# Power_Supply.net
KiCad netlist of a schematic drawn in Altium Designer
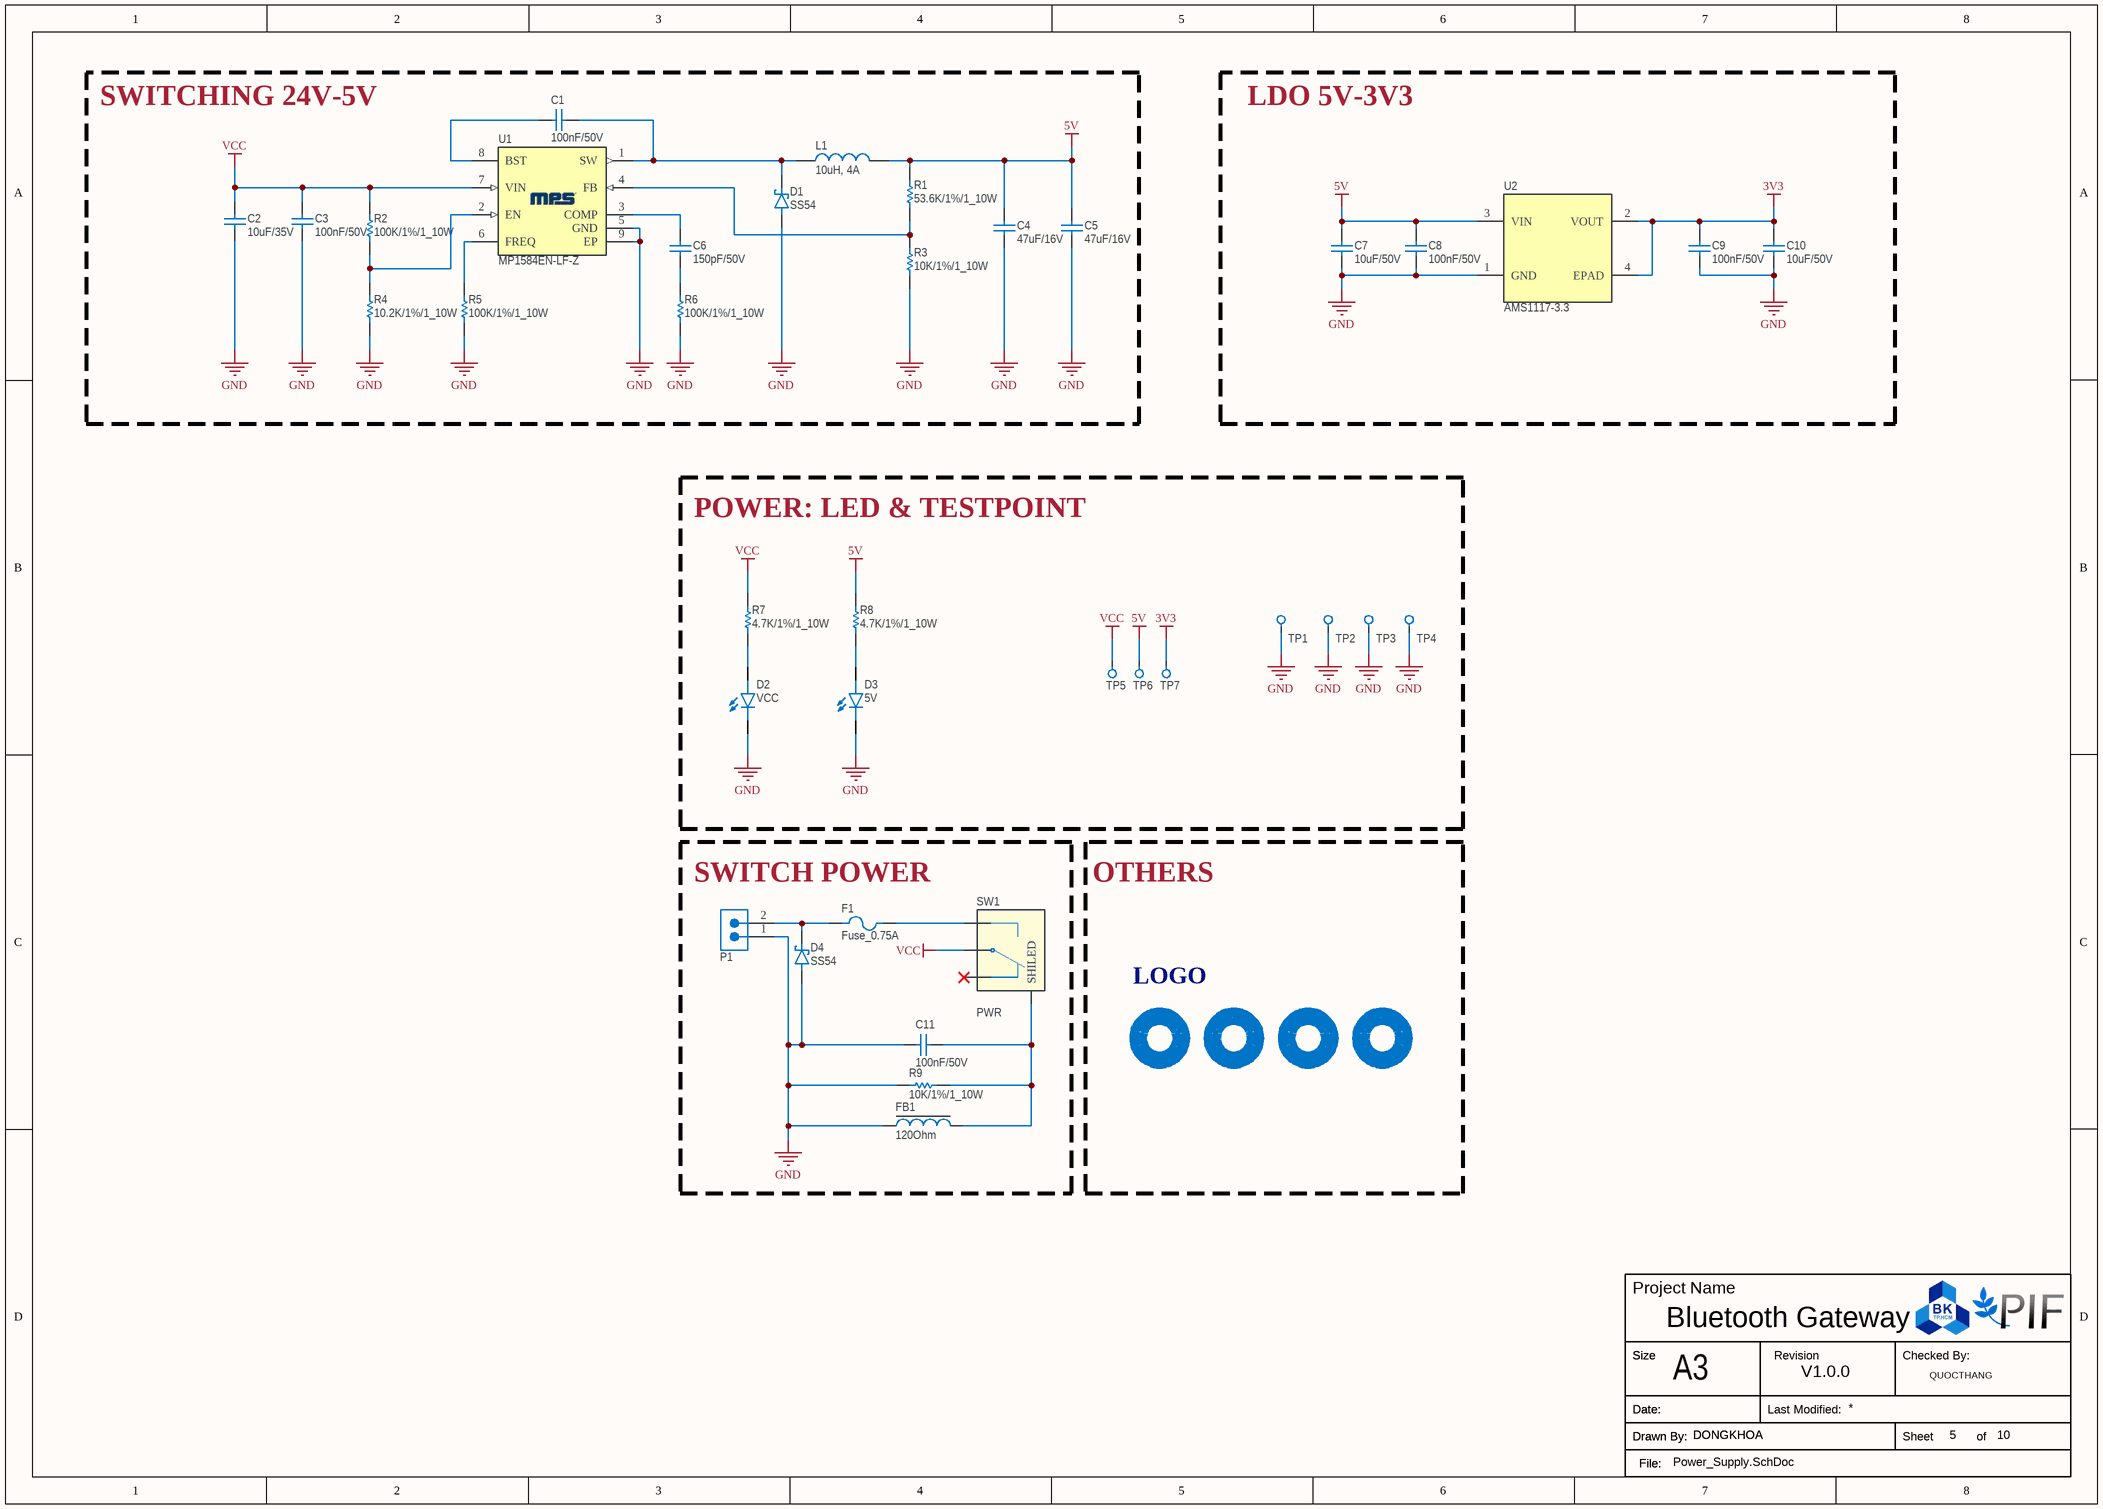
[diagram p0: Power_Supply.SchDoc]

(export (version "E")
  (design (tool "Eeschema 10.0.6"))
  (components
    (comp (ref "*1") (value "LOGO") (footprint "BK_LOGO") (libsource (lib "BluetoothTracking") (part "LOGO")))
    (comp (ref "C1")
      (value "100nF/50V")
      (footprint "CAP_0603")
      (description "CAP, size 0603, 100nF, 50V")
      (fields (field (name "SUPPLY PART NUMBER") "Tụ Gốm 0603 100nF (0.1uF) 50V"))
      (libsource (lib "BluetoothTracking") (part "Ceramic_Cap_100nF_50V_0603"))
    )
    (comp (ref "C2")
      (value "10uF/35V")
      (footprint "CAP_1206")
      (description "CAP, size 1206, 10uF, 35V")
      (fields (field (name "SUPPLY PART NUMBER") "Tụ Gốm 1206 10uF 35V"))
      (libsource (lib "BluetoothTracking") (part "Ceramic_Cap_10uF_35V_1206"))
    )
    (comp (ref "C3")
      (value "100nF/50V")
      (footprint "CAP_1206")
      (description "CAP, size 1206, 100nF, 50V")
      (fields (field (name "SUPPLY PART NUMBER") "Tụ Gốm 1206 100nF (0.1uF) 50V"))
      (libsource (lib "BluetoothTracking") (part "Ceramic_Cap_100nF_50V_1206"))
    )
    (comp (ref "C4")
      (value "47uF/16V")
      (footprint "CAP_1206")
      (description "CAP, size 1206, 47uF, 16V")
      (fields (field (name "SUPPLY PART NUMBER") "Tụ Gốm 1206 47uF 16V"))
      (libsource (lib "BluetoothTracking") (part "Ceramic_Cap_47uF_16V_1206"))
    )
    (comp (ref "C5")
      (value "47uF/16V")
      (footprint "CAP_1206")
      (description "CAP, size 1206, 47uF, 16V")
      (fields (field (name "SUPPLY PART NUMBER") "Tụ Gốm 1206 47uF 16V"))
      (libsource (lib "BluetoothTracking") (part "Ceramic_Cap_47uF_16V_1206"))
    )
    (comp (ref "C6")
      (value "150pF/50V")
      (footprint "CAP_0603")
      (description "CAP, size 0603, 150pF, 50V")
      (fields (field (name "SUPPLY PART NUMBER") "Tụ Gốm 0603 150pF 50V"))
      (libsource (lib "BluetoothTracking") (part "Ceramic_Cap_150pF_50V_0603"))
    )
    (comp (ref "C7")
      (value "10uF/50V")
      (footprint "CAP_0805")
      (description "CAP, size 0805, 10uF, 50V")
      (fields (field (name "SUPPLY PART NUMBER") "Tụ Gốm 0805 10uF 50V"))
      (libsource (lib "BluetoothTracking") (part "Ceramic_Cap_10uF_50V_0805"))
    )
    (comp (ref "C8")
      (value "100nF/50V")
      (footprint "CAP_0805")
      (description "CAP, size 0805, 100nF, 50V")
      (fields (field (name "SUPPLY PART NUMBER") "Tụ Gốm 0805 100nF (0.1uF) 50V"))
      (libsource (lib "BluetoothTracking") (part "Ceramic_Cap_100nF_50V_0805"))
    )
    (comp (ref "C9")
      (value "100nF/50V")
      (footprint "CAP_0805")
      (description "CAP, size 0805, 100nF, 50V")
      (fields (field (name "SUPPLY PART NUMBER") "Tụ Gốm 0805 100nF (0.1uF) 50V"))
      (libsource (lib "BluetoothTracking") (part "Ceramic_Cap_100nF_50V_0805"))
    )
    (comp (ref "C10")
      (value "10uF/50V")
      (footprint "CAP_0805")
      (description "CAP, size 0805, 10uF, 50V")
      (fields (field (name "SUPPLY PART NUMBER") "Tụ Gốm 0805 10uF 50V"))
      (libsource (lib "BluetoothTracking") (part "Ceramic_Cap_10uF_50V_0805"))
    )
    (comp (ref "C11")
      (value "100nF/50V")
      (footprint "CAP_0603")
      (description "CAP, size 0603, 100nF, 50V")
      (fields (field (name "SUPPLY PART NUMBER") "Tụ Gốm 0603 100nF (0.1uF) 50V"))
      (libsource (lib "BluetoothTracking") (part "Ceramic_Cap_100nF_50V_0603"))
    )
    (comp (ref "D1")
      (value "SS54")
      (footprint "D_SMA")
      (description "Diode Schottky 40V 5A Surface Mount SMA")
      (fields (field (name "SUPPLY PART NUMBER") "SS54 SMA Diode Shotky 5A 40V"))
      (libsource (lib "BluetoothTracking") (part "Diode_SS54"))
    )
    (comp (ref "D2")
      (value "VCC")
      (footprint "LED_0603Y")
      (description "LED Yellow 0603")
      (fields (field (name "SUPPLY PART NUMBER") "LED Vàng 0603 Dán SMD Trong Suốt Harvatek"))
      (libsource (lib "BluetoothTracking") (part "LED_Yellow_0603"))
    )
    (comp (ref "D3")
      (value "5V")
      (footprint "LED_0603Y")
      (description "LED Yellow 0603")
      (fields (field (name "SUPPLY PART NUMBER") "LED Vàng 0603 Dán SMD Trong Suốt Harvatek"))
      (libsource (lib "BluetoothTracking") (part "LED_Yellow_0603"))
    )
    (comp (ref "D4")
      (value "SS54")
      (footprint "D_SMA")
      (description "Diode Schottky 40V 5A Surface Mount SMA")
      (fields (field (name "SUPPLY PART NUMBER") "SS54 SMA Diode Shotky 5A 40V"))
      (libsource (lib "BluetoothTracking") (part "Diode_SS54"))
    )
    (comp (ref "F1")
      (value "Fuse_0.75A")
      (footprint "FUSER_MF-MSMF075/24-2")
      (description "MF-MSMF075/24-2 Cầu Chì Tự Phục Hồi 1812 24V 0.75A")
      (libsource (lib "BluetoothTracking") (part "Fuse_24V_0.75A_1812"))
    )
    (comp (ref "FB1")
      (value "120Ohm")
      (footprint "Ferrite_Bead_0805")
      (description "Ferrite Bead, size 0805, 120Ohm, 2A")
      (fields (field (name "SUPPLY PART NUMBER") "CBW201209U121T Ferrite Beads 2A 120 Ohm 0805"))
      (libsource (lib "BluetoothTracking") (part "Ferrite_Bead_120Ohm_2A_0805"))
    )
    (comp (ref "H1")
      (value "Mounting Hole without connection")
      (footprint "MountingHole_3.2mm_M3_Pad_Via")
      (libsource (lib "BluetoothTracking") (part "MountingHole"))
    )
    (comp (ref "H2")
      (value "Mounting Hole without connection")
      (footprint "MountingHole_3.2mm_M3_Pad_Via")
      (libsource (lib "BluetoothTracking") (part "MountingHole"))
    )
    (comp (ref "H3")
      (value "Mounting Hole without connection")
      (footprint "MountingHole_3.2mm_M3_Pad_Via")
      (libsource (lib "BluetoothTracking") (part "MountingHole"))
    )
    (comp (ref "H4")
      (value "Mounting Hole without connection")
      (footprint "MountingHole_3.2mm_M3_Pad_Via")
      (libsource (lib "BluetoothTracking") (part "MountingHole"))
    )
    (comp (ref "L1")
      (value "10uH, 4A")
      (footprint "Inductor_0630")
      (description "10uH, 4A, Size 0630")
      (fields (field (name "SUPPLY PART NUMBER") "Cuộn cảm 10UH 0630"))
      (libsource (lib "BluetoothTracking") (part "IND_10uH_0630"))
    )
    (comp (ref "P1")
      (value "5.08mm_2P")
      (footprint "Terminal_Block_5.08mm_2P")
      (description "Terminal Block THT, pitch 5.08mm, 2p, 300V, 10A")
      (fields
        (field (name "SUPPLY PART NUMBER") "UL-5.08-2-R Terminal Block Plug-in Hàn PCB 2 Chân Cong 5.08mm 300V 15A ULO")
      )
      (libsource (lib "BluetoothTracking") (part "Terminal_Block_5.08mm_2P"))
    )
    (comp (ref "R1")
      (value "53.6K/1%/1_10W")
      (footprint "Resistor_0603")
      (description "Resistor 0603 53.6KOhm 1% 1_10W")
      (fields (field (name "SUPPLY PART NUMBER") "Điện Trở 53.6 KOhm 0603 1%"))
      (libsource (lib "BluetoothTracking") (part "Res_53.6K_0603_1%"))
    )
    (comp (ref "R2")
      (value "100K/1%/1_10W")
      (footprint "Resistor_0603")
      (description "Resistor 0603 100KOhm 1% 1_10W")
      (fields (field (name "SUPPLY PART NUMBER") "Điện Trở 100 KOhm 0603 1%"))
      (libsource (lib "BluetoothTracking") (part "Res_100K_0603_1%"))
    )
    (comp (ref "R3")
      (value "10K/1%/1_10W")
      (footprint "Resistor_0603")
      (description "Resistor 0603 10KOhm 1% 1_10W")
      (fields (field (name "SUPPLY PART NUMBER") "Điện Trở 10 KOhm 0603 1%"))
      (libsource (lib "BluetoothTracking") (part "Res_10K_0603_1%"))
    )
    (comp (ref "R4")
      (value "10.2K/1%/1_10W")
      (footprint "Resistor_0603")
      (description "Resistor 0603 10.2KOhm 1% 1_10W")
      (fields (field (name "SUPPLY PART NUMBER") "Điện Trở 10.2 KOhm 0603 1%"))
      (libsource (lib "BluetoothTracking") (part "Res_10.2K_0603_1%"))
    )
    (comp (ref "R5")
      (value "100K/1%/1_10W")
      (footprint "Resistor_0603")
      (description "Resistor 0603 100KOhm 1% 1_10W")
      (fields (field (name "SUPPLY PART NUMBER") "Điện Trở 100 KOhm 0603 1%"))
      (libsource (lib "BluetoothTracking") (part "Res_100K_0603_1%"))
    )
    (comp (ref "R6")
      (value "100K/1%/1_10W")
      (footprint "Resistor_0603")
      (description "Resistor 0603 100KOhm 1% 1_10W")
      (fields (field (name "SUPPLY PART NUMBER") "Điện Trở 100 KOhm 0603 1%"))
      (libsource (lib "BluetoothTracking") (part "Res_100K_0603_1%"))
    )
    (comp (ref "R7")
      (value "4.7K/1%/1_10W")
      (footprint "Resistor_0603")
      (description "Resistor 0603 4.7KOhm 1% 1_10W")
      (fields (field (name "SUPPLY PART NUMBER") "Điện Trở 4.7 KOhm 0603 1%"))
      (libsource (lib "BluetoothTracking") (part "Res_4.7K_0603_1%"))
    )
    (comp (ref "R8")
      (value "4.7K/1%/1_10W")
      (footprint "Resistor_0603")
      (description "Resistor 0603 4.7KOhm 1% 1_10W")
      (fields (field (name "SUPPLY PART NUMBER") "Điện Trở 4.7 KOhm 0603 1%"))
      (libsource (lib "BluetoothTracking") (part "Res_4.7K_0603_1%"))
    )
    (comp (ref "R9")
      (value "10K/1%/1_10W")
      (footprint "Resistor_0603")
      (description "Resistor 0603 10KOhm 1% 1_10W")
      (fields (field (name "SUPPLY PART NUMBER") "Điện Trở 10 KOhm 0603 1%"))
      (libsource (lib "BluetoothTracking") (part "Res_10K_0603_1%"))
    )
    (comp (ref "SW1")
      (value "PWR")
      (footprint "MTS-102-C3")
      (description "Switch Toggle")
      (fields
        (field (name "SUPPLY PART NUMBER") "MTS-102-C3 Công Tắc Toggle ON-ON Gạt Giữ 3 Chân Cong 6A 125VAC")
      )
      (libsource (lib "BluetoothTracking") (part "MTS-102-C3"))
    )
    (comp (ref "TP1")
      (value "GND")
      (footprint "TestPoint_Pad_3.0x3.0mm")
      (libsource (lib "BluetoothTracking") (part "Testpoint_SMD"))
    )
    (comp (ref "TP2")
      (value "GND1")
      (footprint "TestPoint_Pad_3.0x3.0mm")
      (libsource (lib "BluetoothTracking") (part "Testpoint_SMD"))
    )
    (comp (ref "TP3")
      (value "GND2")
      (footprint "TestPoint_Pad_3.0x3.0mm")
      (libsource (lib "BluetoothTracking") (part "Testpoint_SMD"))
    )
    (comp (ref "TP4")
      (value "GND3")
      (footprint "TestPoint_Pad_3.0x3.0mm")
      (libsource (lib "BluetoothTracking") (part "Testpoint_SMD"))
    )
    (comp (ref "TP5")
      (value "VCC")
      (footprint "TestPoint_Pad_3.0x3.0mm")
      (libsource (lib "BluetoothTracking") (part "Testpoint_SMD"))
    )
    (comp (ref "TP6")
      (value "5V")
      (footprint "TestPoint_Pad_3.0x3.0mm")
      (libsource (lib "BluetoothTracking") (part "Testpoint_SMD"))
    )
    (comp (ref "TP7")
      (value "3V3")
      (footprint "TestPoint_Pad_3.0x3.0mm")
      (libsource (lib "BluetoothTracking") (part "Testpoint_SMD"))
    )
    (comp (ref "U1")
      (value "MP1584EN-LF-Z")
      (footprint "SOIC-8E")
      (libsource (lib "BluetoothTracking") (part "MP1584EN-LF-Z"))
    )
    (comp (ref "U2")
      (value "AMS1117-3.3")
      (footprint "SOT-223")
      (description "No Description Available")
      (libsource (lib "BluetoothTracking") (part "AMS1117-3.3"))
    )
  )
  (nets
    (net (code "1") (name "3V3") (class "Default")
      (node (ref "C10") (pin "2") (pinfunction "2_2") (pintype "passive"))
      (node (ref "C9") (pin "2") (pinfunction "2_2") (pintype "passive"))
      (node (ref "TP7") (pin "1") (pinfunction "1_1") (pintype "passive"))
      (node (ref "U2") (pin "2") (pinfunction "VOUT_2") (pintype "power_in"))
      (node (ref "U2") (pin "4") (pinfunction "EPAD_4") (pintype "power_in"))
    )
    (net (code "2") (name "5V") (class "Default")
      (node (ref "C4") (pin "2") (pinfunction "2_2") (pintype "passive"))
      (node (ref "C5") (pin "2") (pinfunction "2_2") (pintype "passive"))
      (node (ref "C7") (pin "2") (pinfunction "2_2") (pintype "passive"))
      (node (ref "C8") (pin "2") (pinfunction "2_2") (pintype "passive"))
      (node (ref "L1") (pin "2") (pinfunction "2_2") (pintype "passive"))
      (node (ref "R1") (pin "2") (pinfunction "2_2") (pintype "passive"))
      (node (ref "R8") (pin "2") (pinfunction "2_2") (pintype "passive"))
      (node (ref "TP6") (pin "1") (pinfunction "1_1") (pintype "passive"))
      (node (ref "U2") (pin "3") (pinfunction "VIN_3") (pintype "power_in"))
    )
    (net (code "3") (name "GND") (class "Default")
      (node (ref "C10") (pin "1") (pinfunction "1_1") (pintype "passive"))
      (node (ref "C11") (pin "2") (pinfunction "2_2") (pintype "passive"))
      (node (ref "C2") (pin "1") (pinfunction "1_1") (pintype "passive"))
      (node (ref "C3") (pin "1") (pinfunction "1_1") (pintype "passive"))
      (node (ref "C4") (pin "1") (pinfunction "1_1") (pintype "passive"))
      (node (ref "C5") (pin "1") (pinfunction "1_1") (pintype "passive"))
      (node (ref "C7") (pin "1") (pinfunction "1_1") (pintype "passive"))
      (node (ref "C8") (pin "1") (pinfunction "1_1") (pintype "passive"))
      (node (ref "C9") (pin "1") (pinfunction "1_1") (pintype "passive"))
      (node (ref "D1") (pin "2") (pinfunction "A_2") (pintype "passive"))
      (node (ref "D2") (pin "C") (pinfunction "C_C") (pintype "passive"))
      (node (ref "D3") (pin "C") (pinfunction "C_C") (pintype "passive"))
      (node (ref "D4") (pin "2") (pinfunction "A_2") (pintype "passive"))
      (node (ref "FB1") (pin "2") (pinfunction "2_2") (pintype "passive"))
      (node (ref "P1") (pin "1") (pinfunction "1_1") (pintype "passive"))
      (node (ref "R3") (pin "1") (pinfunction "1_1") (pintype "passive"))
      (node (ref "R4") (pin "1") (pinfunction "1_1") (pintype "passive"))
      (node (ref "R5") (pin "1") (pinfunction "1_1") (pintype "passive"))
      (node (ref "R6") (pin "1") (pinfunction "1_1") (pintype "passive"))
      (node (ref "R9") (pin "1") (pinfunction "1_1") (pintype "passive"))
      (node (ref "TP1") (pin "1") (pinfunction "1_1") (pintype "passive"))
      (node (ref "TP2") (pin "1") (pinfunction "1_1") (pintype "passive"))
      (node (ref "TP3") (pin "1") (pinfunction "1_1") (pintype "passive"))
      (node (ref "TP4") (pin "1") (pinfunction "1_1") (pintype "passive"))
      (node (ref "U1") (pin "5") (pinfunction "GND_5") (pintype "power_in"))
      (node (ref "U1") (pin "9") (pinfunction "EP_9") (pintype "power_in"))
      (node (ref "U2") (pin "1") (pinfunction "GND_1") (pintype "power_in"))
    )
    (net (code "4") (name "Net-(C6-Pad1)") (class "Default")
      (node (ref "C6") (pin "1") (pinfunction "1_1") (pintype "passive"))
      (node (ref "R6") (pin "2") (pinfunction "2_2") (pintype "passive"))
    )
    (net (code "5") (name "Net-(D1-C)") (class "Default")
      (node (ref "C1") (pin "2") (pinfunction "2_2") (pintype "passive"))
      (node (ref "D1") (pin "1") (pinfunction "C_1") (pintype "passive"))
      (node (ref "L1") (pin "1") (pinfunction "1_1") (pintype "passive"))
      (node (ref "U1") (pin "1") (pinfunction "SW_1") (pintype "output"))
    )
    (net (code "6") (name "Net-(D2-PadA)") (class "Default")
      (node (ref "D2") (pin "A") (pinfunction "A_A") (pintype "passive"))
      (node (ref "R7") (pin "1") (pinfunction "1_1") (pintype "passive"))
    )
    (net (code "7") (name "Net-(D3-PadA)") (class "Default")
      (node (ref "D3") (pin "A") (pinfunction "A_A") (pintype "passive"))
      (node (ref "R8") (pin "1") (pinfunction "1_1") (pintype "passive"))
    )
    (net (code "8") (name "Net-(D4-C)") (class "Default")
      (node (ref "D4") (pin "1") (pinfunction "C_1") (pintype "passive"))
      (node (ref "F1") (pin "1") (pinfunction "1_1") (pintype "passive"))
      (node (ref "P1") (pin "2") (pinfunction "2_2") (pintype "passive"))
    )
    (net (code "9") (name "Net-(F1-Pad2)") (class "Default")
      (node (ref "F1") (pin "2") (pinfunction "2_2") (pintype "passive"))
      (node (ref "SW1") (pin "3") (pinfunction "3_3") (pintype "passive"))
    )
    (net (code "10") (name "Net-(SW1-SHILED)") (class "Default")
      (node (ref "C11") (pin "1") (pinfunction "1_1") (pintype "passive"))
      (node (ref "FB1") (pin "1") (pinfunction "1_1") (pintype "passive"))
      (node (ref "R9") (pin "2") (pinfunction "2_2") (pintype "passive"))
      (node (ref "SW1") (pin "SH") (pinfunction "SHILED_SH") (pintype "passive"))
    )
    (net (code "11") (name "Net-(U1-BST)") (class "Default")
      (node (ref "C1") (pin "1") (pinfunction "1_1") (pintype "passive"))
      (node (ref "U1") (pin "8") (pinfunction "BST_8") (pintype "passive"))
    )
    (net (code "12") (name "Net-(U1-COMP)") (class "Default")
      (node (ref "C6") (pin "2") (pinfunction "2_2") (pintype "passive"))
      (node (ref "U1") (pin "3") (pinfunction "COMP_3") (pintype "passive"))
    )
    (net (code "13") (name "Net-(U1-EN)") (class "Default")
      (node (ref "R2") (pin "1") (pinfunction "1_1") (pintype "passive"))
      (node (ref "R4") (pin "2") (pinfunction "2_2") (pintype "passive"))
      (node (ref "U1") (pin "2") (pinfunction "EN_2") (pintype "input"))
    )
    (net (code "14") (name "Net-(U1-FB)") (class "Default")
      (node (ref "R1") (pin "1") (pinfunction "1_1") (pintype "passive"))
      (node (ref "R3") (pin "2") (pinfunction "2_2") (pintype "passive"))
      (node (ref "U1") (pin "4") (pinfunction "FB_4") (pintype "input"))
    )
    (net (code "15") (name "Net-(U1-FREQ)") (class "Default")
      (node (ref "R5") (pin "2") (pinfunction "2_2") (pintype "passive"))
      (node (ref "U1") (pin "6") (pinfunction "FREQ_6") (pintype "passive"))
    )
    (net (code "16") (name "VCC") (class "Default")
      (node (ref "C2") (pin "2") (pinfunction "2_2") (pintype "passive"))
      (node (ref "C3") (pin "2") (pinfunction "2_2") (pintype "passive"))
      (node (ref "R2") (pin "2") (pinfunction "2_2") (pintype "passive"))
      (node (ref "R7") (pin "2") (pinfunction "2_2") (pintype "passive"))
      (node (ref "SW1") (pin "2") (pinfunction "2_2") (pintype "passive"))
      (node (ref "TP5") (pin "1") (pinfunction "1_1") (pintype "passive"))
      (node (ref "U1") (pin "7") (pinfunction "VIN_7") (pintype "input"))
    )
    (net (code "17") (name "unconnected-(SW1-Pad1)") (class "Default")
      (node (ref "SW1") (pin "1") (pinfunction "1_1") (pintype "passive+no_connect"))
    )
  )
)
